# v1.net
KiCad netlist of a schematic drawn in Altium Designer
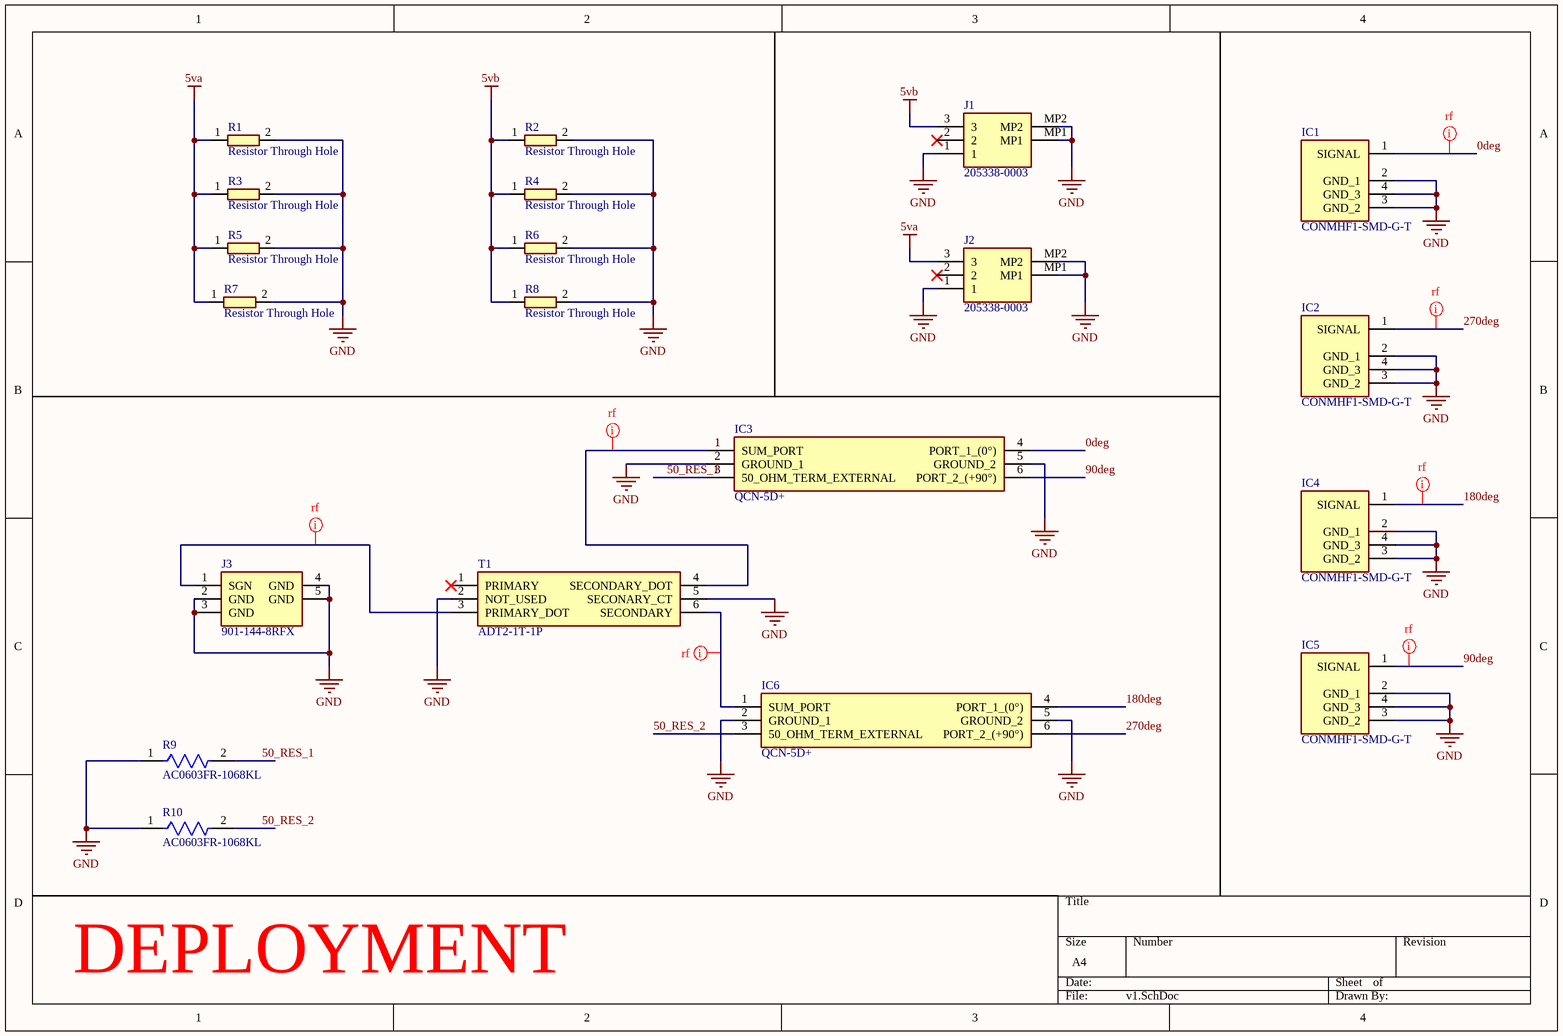
[diagram p0: v1.SchDoc]

(export (version "E")
  (design (tool "Eeschema 10.0.6"))
  (components
    (comp (ref "IC1")
      (value "CONMHF1-SMD-G-T")
      (footprint "CONMHF1SMDGT")
      (description "Integrated Circuit")
      (fields (field (name "MOUSER PART NUMBER") "712-CONMHF1-SMD-G-T"))
      (libsource (lib "SamacSys") (part "CONMHF1-SMD-G-T"))
    )
    (comp (ref "IC2")
      (value "CONMHF1-SMD-G-T")
      (footprint "CONMHF1SMDGT")
      (description "Integrated Circuit")
      (fields (field (name "MOUSER PART NUMBER") "712-CONMHF1-SMD-G-T"))
      (libsource (lib "SamacSys") (part "CONMHF1-SMD-G-T"))
    )
    (comp (ref "IC3")
      (value "QCN-5D+")
      (footprint "QCN5D")
      (description "Integrated Circuit")
      (fields (field (name "MOUSER PART NUMBER") "139-QCN-5D"))
      (libsource (lib "SamacSys") (part "QCN-5D+"))
    )
    (comp (ref "IC4")
      (value "CONMHF1-SMD-G-T")
      (footprint "CONMHF1SMDGT")
      (description "Integrated Circuit")
      (fields (field (name "MOUSER PART NUMBER") "712-CONMHF1-SMD-G-T"))
      (libsource (lib "SamacSys") (part "CONMHF1-SMD-G-T"))
    )
    (comp (ref "IC5")
      (value "CONMHF1-SMD-G-T")
      (footprint "CONMHF1SMDGT")
      (description "Integrated Circuit")
      (fields (field (name "MOUSER PART NUMBER") "712-CONMHF1-SMD-G-T"))
      (libsource (lib "SamacSys") (part "CONMHF1-SMD-G-T"))
    )
    (comp (ref "IC6")
      (value "QCN-5D+")
      (footprint "QCN5D")
      (description "Integrated Circuit")
      (fields (field (name "MOUSER PART NUMBER") "139-QCN-5D"))
      (libsource (lib "SamacSys") (part "QCN-5D+"))
    )
    (comp (ref "J1")
      (value "205338-0003")
      (footprint "SamacSys:2053380003")
      (description "Connector")
      (fields (field (name "MOUSER PART NUMBER") "538-205338-0003"))
      (libsource (lib "*") (part "205338-0003"))
    )
    (comp (ref "J2")
      (value "205338-0003")
      (footprint "SamacSys:2053380003")
      (description "Connector")
      (fields (field (name "MOUSER PART NUMBER") "538-205338-0003"))
      (libsource (lib "SamacSys") (part "205338-0003"))
    )
    (comp (ref "J3")
      (value "901-144-8RFX")
      (footprint "SamacSys:9011448RFX")
      (description "Connector")
      (fields (field (name "MOUSER PART NUMBER") "523-901-144-8RFX"))
      (libsource (lib "SamacSys") (part "901-144-8RFX"))
    )
    (comp (ref "R1")
      (value "Resistor Through Hole")
      (footprint "ResistoR THROUGHHOLE")
      (libsource (lib "STeRG-Passives-Standard") (part "Resistor"))
    )
    (comp (ref "R2")
      (value "Resistor Through Hole")
      (footprint "ResistoR THROUGHHOLE")
      (libsource (lib "STeRG-Passives-Standard") (part "Resistor"))
    )
    (comp (ref "R3")
      (value "Resistor Through Hole")
      (footprint "ResistoR THROUGHHOLE")
      (libsource (lib "STeRG-Passives-Standard") (part "Resistor"))
    )
    (comp (ref "R4")
      (value "Resistor Through Hole")
      (footprint "ResistoR THROUGHHOLE")
      (libsource (lib "STeRG-Passives-Standard") (part "Resistor"))
    )
    (comp (ref "R5")
      (value "Resistor Through Hole")
      (footprint "ResistoR THROUGHHOLE")
      (libsource (lib "STeRG-Passives-Standard") (part "Resistor"))
    )
    (comp (ref "R6")
      (value "Resistor Through Hole")
      (footprint "ResistoR THROUGHHOLE")
      (libsource (lib "STeRG-Passives-Standard") (part "Resistor"))
    )
    (comp (ref "R7")
      (value "Resistor Through Hole")
      (footprint "ResistoR THROUGHHOLE")
      (libsource (lib "STeRG-Passives-Standard") (part "Resistor"))
    )
    (comp (ref "R8")
      (value "Resistor Through Hole")
      (footprint "ResistoR THROUGHHOLE")
      (libsource (lib "STeRG-Passives-Standard") (part "Resistor"))
    )
    (comp (ref "R9")
      (value "AC0603FR-1068KL")
      (footprint "FP-AC0603-IPC_A")
      (description "RES 68KΩ 1.00% 0.1W 0603")
      (libsource (lib "Altium Content Vault") (part "1029c3af85768c4190bb7ad29bc67b5"))
    )
    (comp (ref "R10")
      (value "AC0603FR-1068KL")
      (footprint "FP-AC0603-IPC_A")
      (description "RES 68KΩ 1.00% 0.1W 0603")
      (libsource (lib "Altium Content Vault") (part "1029c3af85768c4190bb7ad29bc67b5"))
    )
    (comp (ref "T1")
      (value "ADT2-1T-1P")
      (footprint "SamacSys:SOTFL254P691X284-6N")
      (description "Transformer")
      (libsource (lib "*") (part "ADT2-1T-1P"))
    )
  )
  (nets
    (net (code "1") (name "/0deg") (class "Default")
      (node (ref "IC1") (pin "1") (pinfunction "SIGNAL_1") (pintype "passive"))
      (node (ref "IC3") (pin "4") (pinfunction "PORT_1_(0°)_4") (pintype "passive"))
    )
    (net (code "2") (name "/50_RES_1") (class "Default")
      (node (ref "IC3") (pin "3") (pinfunction "50_OHM_TERM_EXTERNAL_3") (pintype "passive"))
      (node (ref "R9") (pin "2") (pinfunction "2_2") (pintype "passive"))
    )
    (net (code "3") (name "/50_RES_2") (class "Default")
      (node (ref "IC6") (pin "3") (pinfunction "50_OHM_TERM_EXTERNAL_3") (pintype "passive"))
      (node (ref "R10") (pin "2") (pinfunction "2_2") (pintype "passive"))
    )
    (net (code "4") (name "/90deg") (class "Default")
      (node (ref "IC3") (pin "6") (pinfunction "PORT_2_(+90°)_6") (pintype "passive"))
      (node (ref "IC5") (pin "1") (pinfunction "SIGNAL_1") (pintype "passive"))
    )
    (net (code "5") (name "/180deg") (class "Default")
      (node (ref "IC4") (pin "1") (pinfunction "SIGNAL_1") (pintype "passive"))
      (node (ref "IC6") (pin "4") (pinfunction "PORT_1_(0°)_4") (pintype "passive"))
    )
    (net (code "6") (name "/270deg") (class "Default")
      (node (ref "IC2") (pin "1") (pinfunction "SIGNAL_1") (pintype "passive"))
      (node (ref "IC6") (pin "6") (pinfunction "PORT_2_(+90°)_6") (pintype "passive"))
    )
    (net (code "7") (name "5va") (class "Default")
      (node (ref "J2") (pin "3") (pinfunction "3_3") (pintype "passive"))
      (node (ref "R1") (pin "1") (pintype "passive"))
      (node (ref "R3") (pin "1") (pintype "passive"))
      (node (ref "R5") (pin "1") (pintype "passive"))
      (node (ref "R7") (pin "1") (pintype "passive"))
    )
    (net (code "8") (name "5vb") (class "Default")
      (node (ref "J1") (pin "3") (pinfunction "3_3") (pintype "passive"))
      (node (ref "R2") (pin "1") (pintype "passive"))
      (node (ref "R4") (pin "1") (pintype "passive"))
      (node (ref "R6") (pin "1") (pintype "passive"))
      (node (ref "R8") (pin "1") (pintype "passive"))
    )
    (net (code "9") (name "GND") (class "Default")
      (node (ref "IC1") (pin "2") (pinfunction "GND_1_2") (pintype "passive"))
      (node (ref "IC1") (pin "3") (pinfunction "GND_2_3") (pintype "passive"))
      (node (ref "IC1") (pin "4") (pinfunction "GND_3_4") (pintype "passive"))
      (node (ref "IC2") (pin "2") (pinfunction "GND_1_2") (pintype "passive"))
      (node (ref "IC2") (pin "3") (pinfunction "GND_2_3") (pintype "passive"))
      (node (ref "IC2") (pin "4") (pinfunction "GND_3_4") (pintype "passive"))
      (node (ref "IC3") (pin "2") (pinfunction "GROUND_1_2") (pintype "passive"))
      (node (ref "IC3") (pin "5") (pinfunction "GROUND_2_5") (pintype "passive"))
      (node (ref "IC4") (pin "2") (pinfunction "GND_1_2") (pintype "passive"))
      (node (ref "IC4") (pin "3") (pinfunction "GND_2_3") (pintype "passive"))
      (node (ref "IC4") (pin "4") (pinfunction "GND_3_4") (pintype "passive"))
      (node (ref "IC5") (pin "2") (pinfunction "GND_1_2") (pintype "passive"))
      (node (ref "IC5") (pin "3") (pinfunction "GND_2_3") (pintype "passive"))
      (node (ref "IC5") (pin "4") (pinfunction "GND_3_4") (pintype "passive"))
      (node (ref "IC6") (pin "2") (pinfunction "GROUND_1_2") (pintype "passive"))
      (node (ref "IC6") (pin "5") (pinfunction "GROUND_2_5") (pintype "passive"))
      (node (ref "J1") (pin "1") (pinfunction "1_1") (pintype "passive"))
      (node (ref "J1") (pin "MP1") (pinfunction "MP1_MP1") (pintype "passive"))
      (node (ref "J1") (pin "MP2") (pinfunction "MP2_MP2") (pintype "passive"))
      (node (ref "J2") (pin "1") (pinfunction "1_1") (pintype "passive"))
      (node (ref "J2") (pin "MP1") (pinfunction "MP1_MP1") (pintype "passive"))
      (node (ref "J2") (pin "MP2") (pinfunction "MP2_MP2") (pintype "passive"))
      (node (ref "J3") (pin "2") (pinfunction "GND_2") (pintype "passive"))
      (node (ref "J3") (pin "3") (pinfunction "GND_3") (pintype "passive"))
      (node (ref "J3") (pin "4") (pinfunction "GND_4") (pintype "passive"))
      (node (ref "J3") (pin "5") (pinfunction "GND_5") (pintype "passive"))
      (node (ref "R1") (pin "2") (pintype "passive"))
      (node (ref "R10") (pin "1") (pinfunction "1_1") (pintype "passive"))
      (node (ref "R2") (pin "2") (pintype "passive"))
      (node (ref "R3") (pin "2") (pintype "passive"))
      (node (ref "R4") (pin "2") (pintype "passive"))
      (node (ref "R5") (pin "2") (pintype "passive"))
      (node (ref "R6") (pin "2") (pintype "passive"))
      (node (ref "R7") (pin "2") (pintype "passive"))
      (node (ref "R8") (pin "2") (pintype "passive"))
      (node (ref "R9") (pin "1") (pinfunction "1_1") (pintype "passive"))
      (node (ref "T1") (pin "2") (pinfunction "NOT_USED_2") (pintype "passive"))
      (node (ref "T1") (pin "5") (pinfunction "SECONARY_CT_5") (pintype "passive"))
    )
    (net (code "10") (name "Net-(IC3-SUM_PORT)") (class "Default")
      (node (ref "IC3") (pin "1") (pinfunction "SUM_PORT_1") (pintype "passive"))
      (node (ref "T1") (pin "4") (pinfunction "SECONDARY_DOT_4") (pintype "passive"))
    )
    (net (code "11") (name "Net-(IC6-SUM_PORT)") (class "Default")
      (node (ref "IC6") (pin "1") (pinfunction "SUM_PORT_1") (pintype "passive"))
      (node (ref "T1") (pin "6") (pinfunction "SECONDARY_6") (pintype "passive"))
    )
    (net (code "12") (name "Net-(J3-SGN)") (class "Default")
      (node (ref "J3") (pin "1") (pinfunction "SGN_1") (pintype "passive"))
      (node (ref "T1") (pin "3") (pinfunction "PRIMARY_DOT_3") (pintype "passive"))
    )
    (net (code "13") (name "unconnected-(J1-Pad2)") (class "Default")
      (node (ref "J1") (pin "2") (pinfunction "2_2") (pintype "passive+no_connect"))
    )
    (net (code "14") (name "unconnected-(J2-Pad2)") (class "Default")
      (node (ref "J2") (pin "2") (pinfunction "2_2") (pintype "passive+no_connect"))
    )
    (net (code "15") (name "unconnected-(T1-PRIMARY-Pad1)") (class "Default")
      (node (ref "T1") (pin "1") (pinfunction "PRIMARY_1") (pintype "passive+no_connect"))
    )
  )
)
